# Sheet1.net
KiCad netlist of a schematic drawn in Altium Designer
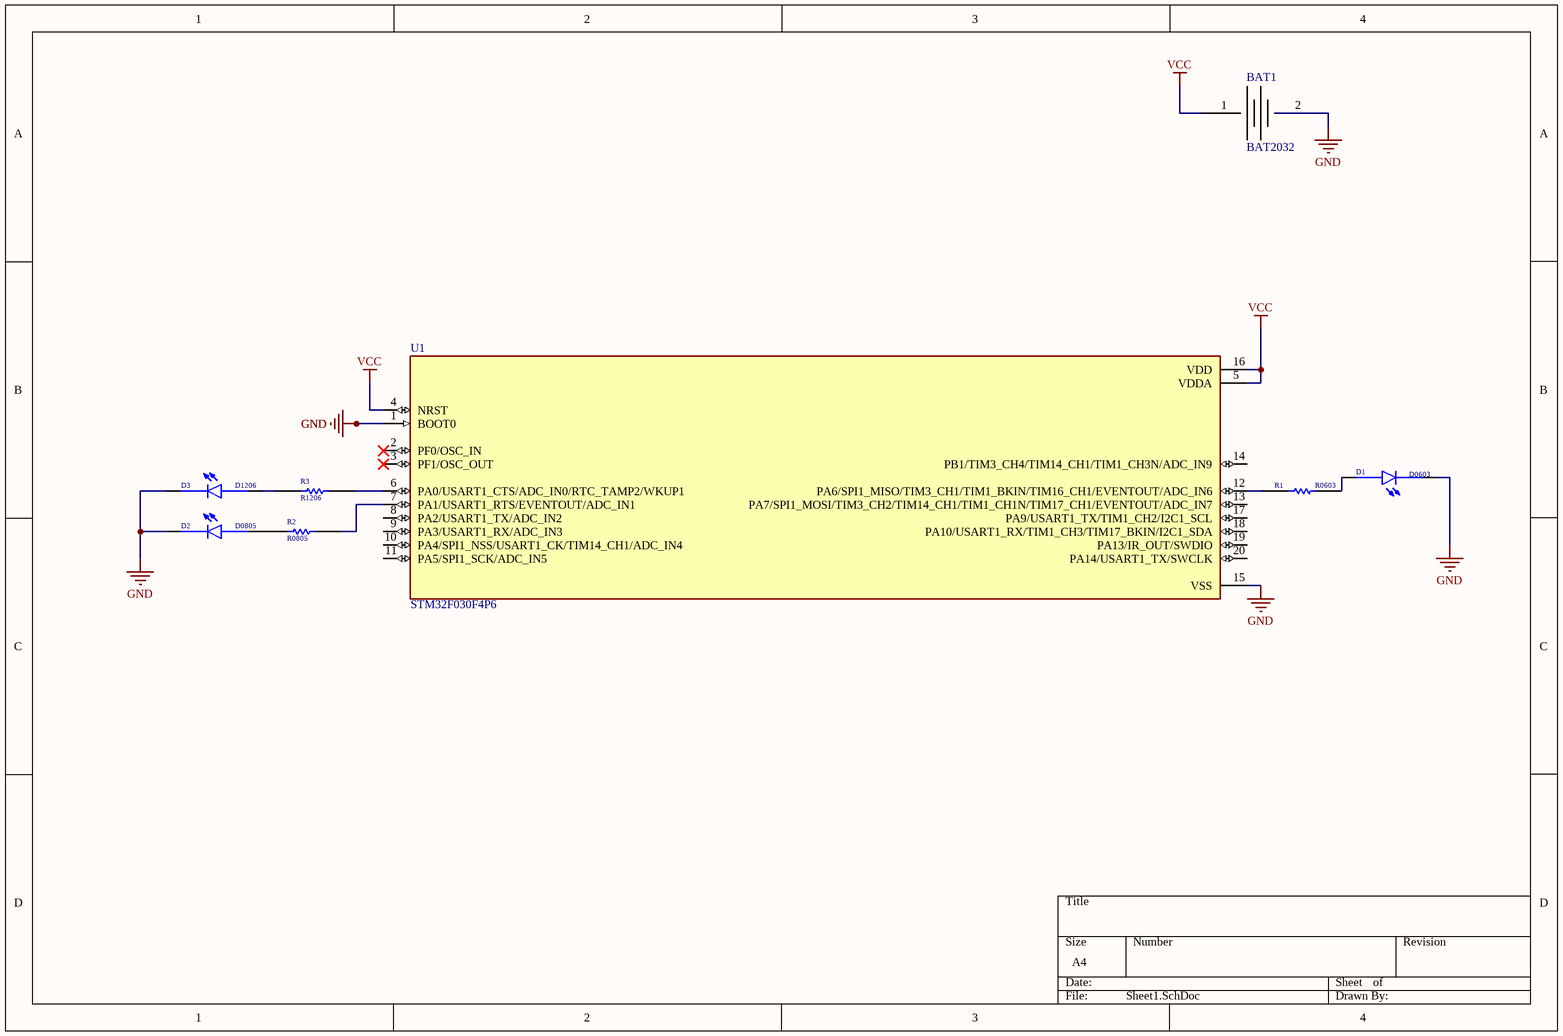
[diagram p0: Sheet1.SchDoc]

(export (version "E")
  (design (tool "Eeschema 10.0.6"))
  (components
    (comp (ref "BAT1")
      (value "BAT2032")
      (footprint "PCBComponent_1")
      (description "Cell coin 2032")
      (libsource (lib "Bat2032") (part "BAT2032"))
    )
    (comp (ref "D1")
      (value "D0603")
      (footprint "LEDC1608X65N")
      (description "White LED Indication - Discrete 3.1V 0603 _1608 Metric_")
      (fields (field (name "MP") "LTW-C191TLA") (field (name "MF") "Lite-On"))
      (libsource (lib "D0603") (part "D0603"))
    )
    (comp (ref "D2")
      (value "D0805")
      (footprint "MY_0805")
      (description "White LED Indication - Discrete 2.9V 0805 _2012 Metric_")
      (fields (field (name "MP") "SMLMN2WB1CW1C") (field (name "MF") "Rohm Semiconductor"))
      (libsource (lib "D0805") (part "D0805"))
    )
    (comp (ref "D3")
      (value "D1206")
      (footprint "MY_1206")
      (description "Red 631nm LED Indication - Discrete 2V 1206 _3216 Metric_")
      (fields (field (name "MF") "Lite-On Inc.") (field (name "DIGI-KEY_PART_NUMBER") "160-1457-1-ND"))
      (libsource (lib "D1206") (part "D1206"))
    )
    (comp (ref "R1")
      (value "R0603")
      (footprint "RESC1508X55N")
      (description "0 Ohms Jumper 0.1W, 1/10W Chip Resistor 0603 _1608 Metric_ Automotive AEC-Q200 Thick Film")
      (fields (field (name "MP") "RMCF0603ZT0R00") (field (name "MF") "Stackpole Electronics Inc"))
      (libsource (lib "R0603") (part "R0603"))
    )
    (comp (ref "R2")
      (value "R0805")
      (footprint "RESC2012X60")
      (description "0 Ohms Jumper 0.125W, 1/8W Chip Resistor 0805 (2012 Metric) Moisture Resistant Thick Film")
      (fields (field (name "MF") "Yageo") (field (name "MP") "RC0805JR-070RL"))
      (libsource (lib "R0805") (part "R0805"))
    )
    (comp (ref "R3")
      (value "R1206")
      (footprint "RESC3116X65N")
      (description "22 Ohms Â±5% 0.25W, 1/4W Chip Resistor 1206 (3216 Metric) Thick Film")
      (fields (field (name "MP") "RC1206JR-0722RL") (field (name "MF") "Yageo"))
      (libsource (lib "R1206") (part "R1206"))
    )
    (comp (ref "U1")
      (value "STM32F030F4P6")
      (footprint "SOP65P640X120-20N")
      (description "ARMÂ® CortexÂ®-M0 STM32F0 Microcontroller IC 32-Bit 48MHz 16KB _16K x 8_ FLASH")
      (fields (field (name "MF") "STMicroelectronics") (field (name "DIGI-KEY_PART_NUMBER") "497-14044-5-ND"))
      (libsource (lib "STM32F030F4P6") (part "STM32F030F4P6"))
    )
  )
  (nets
    (net (code "1") (name "GND") (class "Default")
      (node (ref "BAT1") (pin "2") (pinfunction "2_2") (pintype "power_in"))
      (node (ref "D1") (pin "C") (pinfunction "C_C") (pintype "passive"))
      (node (ref "D2") (pin "C") (pinfunction "C_C") (pintype "passive"))
      (node (ref "D3") (pin "C") (pinfunction "C_C") (pintype "passive"))
      (node (ref "U1") (pin "1") (pinfunction "BOOT0_1") (pintype "input"))
      (node (ref "U1") (pin "15") (pinfunction "VSS_15") (pintype "power_in"))
    )
    (net (code "2") (name "Net-(D1-PadA)") (class "Default")
      (node (ref "D1") (pin "A") (pinfunction "A_A") (pintype "passive"))
      (node (ref "R1") (pin "2") (pinfunction "2_2") (pintype "passive"))
    )
    (net (code "3") (name "Net-(D2-PadA)") (class "Default")
      (node (ref "D2") (pin "A") (pinfunction "A_A") (pintype "passive"))
      (node (ref "R2") (pin "2") (pinfunction "2_2") (pintype "passive"))
    )
    (net (code "4") (name "Net-(D3-PadA)") (class "Default")
      (node (ref "D3") (pin "A") (pinfunction "A_A") (pintype "passive"))
      (node (ref "R3") (pin "2") (pinfunction "2_2") (pintype "passive"))
    )
    (net (code "5") (name "Net-(U1-PA0{slash}USART1_CTS{slash}ADC_IN0{slash}RTC_TAMP2{slash}WKUP1)") (class "Default")
      (node (ref "R3") (pin "1") (pinfunction "1_1") (pintype "passive"))
      (node (ref "U1") (pin "6") (pinfunction "PA0/USART1_CTS/ADC_IN0/RTC_TAMP2/WKUP1_6") (pintype "bidirectional"))
    )
    (net (code "6") (name "Net-(U1-PA1{slash}USART1_RTS{slash}EVENTOUT{slash}ADC_IN1)") (class "Default")
      (node (ref "R2") (pin "1") (pinfunction "1_1") (pintype "passive"))
      (node (ref "U1") (pin "7") (pinfunction "PA1/USART1_RTS/EVENTOUT/ADC_IN1_7") (pintype "bidirectional"))
    )
    (net (code "7") (name "Net-(U1-PA6{slash}SPI1_MISO{slash}TIM3_CH1{slash}TIM1_BKIN{slash}TIM16_CH1{slash}EVENTOUT{slash}ADC_IN6)") (class "Default")
      (node (ref "R1") (pin "1") (pinfunction "1_1") (pintype "passive"))
      (node (ref "U1") (pin "12") (pinfunction "PA6/SPI1_MISO/TIM3_CH1/TIM1_BKIN/TIM16_CH1/EVENTOUT/ADC_IN6_12") (pintype "bidirectional"))
    )
    (net (code "8") (name "VCC") (class "Default")
      (node (ref "BAT1") (pin "1") (pinfunction "1_1") (pintype "power_in"))
      (node (ref "U1") (pin "16") (pinfunction "VDD_16") (pintype "power_in"))
      (node (ref "U1") (pin "4") (pinfunction "NRST_4") (pintype "bidirectional"))
      (node (ref "U1") (pin "5") (pinfunction "VDDA_5") (pintype "power_in"))
    )
    (net (code "9") (name "unconnected-(U1-PA2{slash}USART1_TX{slash}ADC_IN2-Pad8)") (class "Default")
      (node (ref "U1") (pin "8") (pinfunction "PA2/USART1_TX/ADC_IN2_8") (pintype "bidirectional"))
    )
    (net (code "10") (name "unconnected-(U1-PA3{slash}USART1_RX{slash}ADC_IN3-Pad9)") (class "Default")
      (node (ref "U1") (pin "9") (pinfunction "PA3/USART1_RX/ADC_IN3_9") (pintype "bidirectional"))
    )
    (net (code "11") (name "unconnected-(U1-PA4{slash}SPI1_NSS{slash}USART1_CK{slash}TIM14_CH1{slash}ADC_IN4-Pad10)") (class "Default")
      (node (ref "U1") (pin "10") (pinfunction "PA4/SPI1_NSS/USART1_CK/TIM14_CH1/ADC_IN4_10") (pintype "bidirectional"))
    )
    (net (code "12") (name "unconnected-(U1-PA5{slash}SPI1_SCK{slash}ADC_IN5-Pad11)") (class "Default")
      (node (ref "U1") (pin "11") (pinfunction "PA5/SPI1_SCK/ADC_IN5_11") (pintype "bidirectional"))
    )
    (net (code "13") (name "unconnected-(U1-PA7{slash}SPI1_MOSI{slash}TIM3_CH2{slash}TIM14_CH1{slash}TIM1_CH1N{slash}TIM17_CH1{slash}EVENTOUT{slash}ADC_IN7-Pad13)") (class "Default")
      (node (ref "U1") (pin "13") (pinfunction "PA7/SPI1_MOSI/TIM3_CH2/TIM14_CH1/TIM1_CH1N/TIM17_CH1/EVENTOUT/ADC_IN7_13") (pintype "bidirectional"))
    )
    (net (code "14") (name "unconnected-(U1-PA9{slash}USART1_TX{slash}TIM1_CH2{slash}I2C1_SCL-Pad17)") (class "Default")
      (node (ref "U1") (pin "17") (pinfunction "PA9/USART1_TX/TIM1_CH2/I2C1_SCL_17") (pintype "bidirectional"))
    )
    (net (code "15") (name "unconnected-(U1-PA10{slash}USART1_RX{slash}TIM1_CH3{slash}TIM17_BKIN{slash}I2C1_SDA-Pad18)") (class "Default")
      (node (ref "U1") (pin "18") (pinfunction "PA10/USART1_RX/TIM1_CH3/TIM17_BKIN/I2C1_SDA_18") (pintype "bidirectional"))
    )
    (net (code "16") (name "unconnected-(U1-PA13{slash}IR_OUT{slash}SWDIO-Pad19)") (class "Default")
      (node (ref "U1") (pin "19") (pinfunction "PA13/IR_OUT/SWDIO_19") (pintype "bidirectional"))
    )
    (net (code "17") (name "unconnected-(U1-PA14{slash}USART1_TX{slash}SWCLK-Pad20)") (class "Default")
      (node (ref "U1") (pin "20") (pinfunction "PA14/USART1_TX/SWCLK_20") (pintype "bidirectional"))
    )
    (net (code "18") (name "unconnected-(U1-PB1{slash}TIM3_CH4{slash}TIM14_CH1{slash}TIM1_CH3N{slash}ADC_IN9-Pad14)") (class "Default")
      (node (ref "U1") (pin "14") (pinfunction "PB1/TIM3_CH4/TIM14_CH1/TIM1_CH3N/ADC_IN9_14") (pintype "bidirectional"))
    )
    (net (code "19") (name "unconnected-(U1-PF0{slash}OSC_IN-Pad2)") (class "Default")
      (node (ref "U1") (pin "2") (pinfunction "PF0/OSC_IN_2") (pintype "bidirectional+no_connect"))
    )
    (net (code "20") (name "unconnected-(U1-PF1{slash}OSC_OUT-Pad3)") (class "Default")
      (node (ref "U1") (pin "3") (pinfunction "PF1/OSC_OUT_3") (pintype "bidirectional+no_connect"))
    )
  )
)
